# CAN.net
KiCad netlist of a schematic drawn in Altium Designer
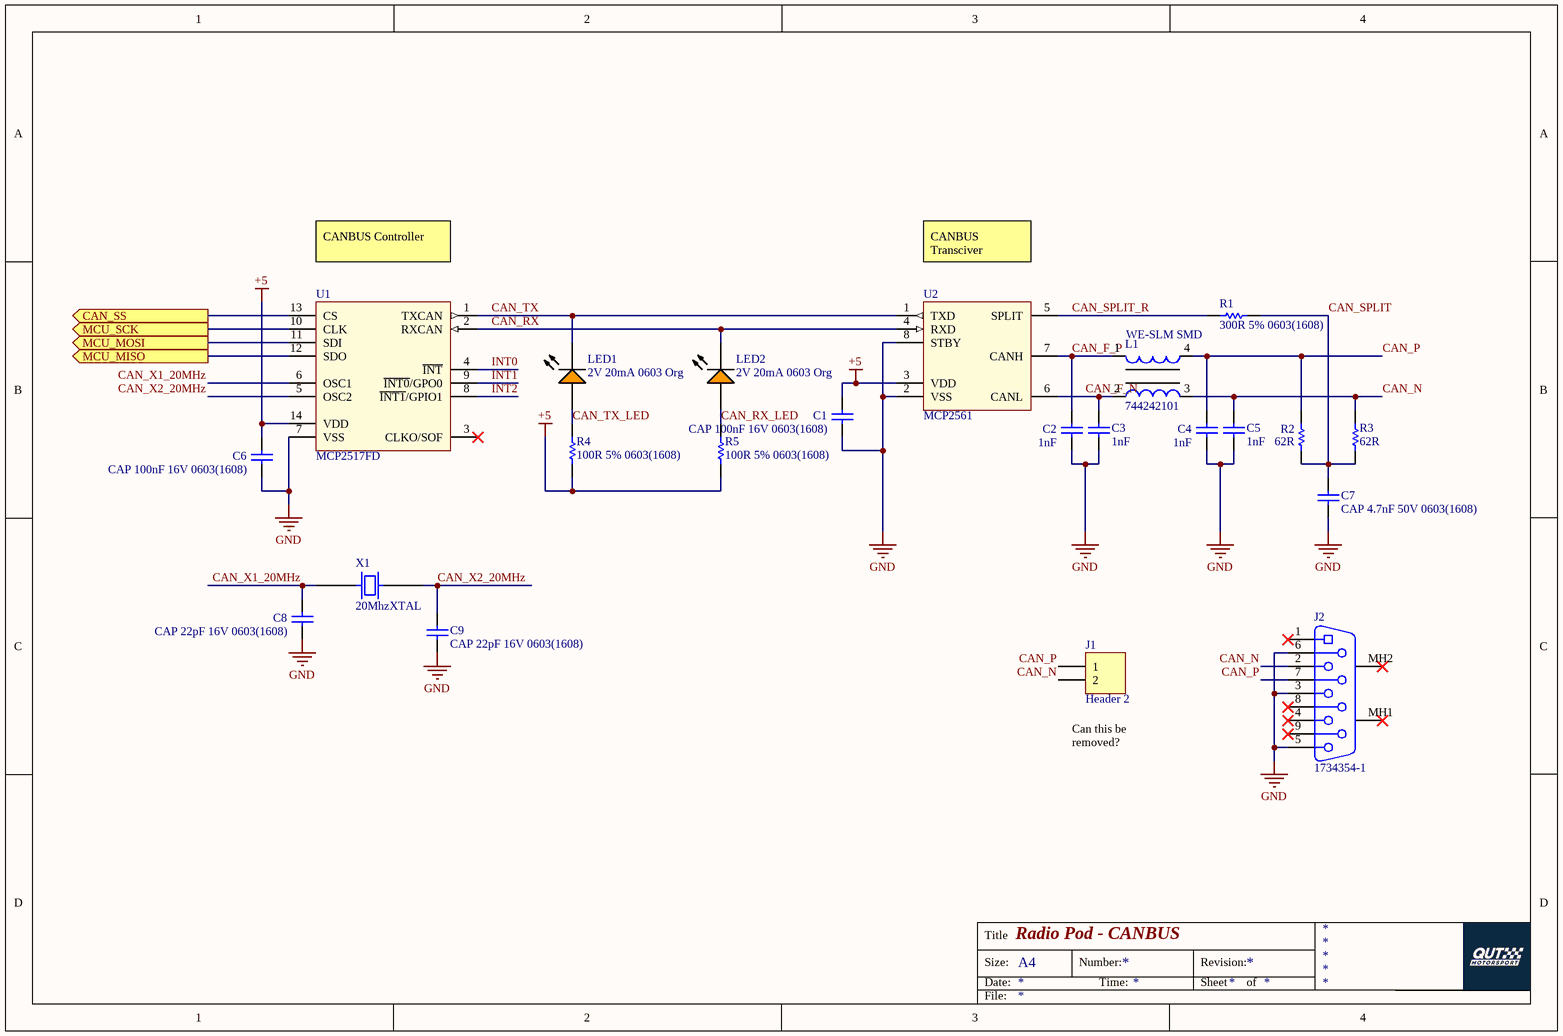
[diagram p0: CAN.SchDoc]

(export (version "E")
  (design (tool "Eeschema 10.0.6"))
  (components
    (comp (ref "C1")
      (value "CAP 100nF 16V 0603(1608)")
      (footprint "CAPC0603(1608)100_N")
      (description "CAP 100nF 16V ±10% 0603 (1608 Metric) Thickness 1mm SMD")
      (fields (field (name "TOLERANCE") "Â±10%"))
      (libsource (lib "Altium Content Vault") (part "CAP"))
    )
    (comp (ref "C2")
      (value "1nF")
      (footprint "CAPC0603(1608)100_M")
      (description "CAP 1nF 16V ±5% 0603 (1608 Metric) Thickness 1mm SMD")
      (fields (field (name "TOLERANCE") "Â±5%"))
      (libsource (lib "Altium Content Vault") (part "CAP"))
    )
    (comp (ref "C3")
      (value "1nF")
      (footprint "CAPC0603(1608)100_M")
      (description "CAP 1nF 16V ±5% 0603 (1608 Metric) Thickness 1mm SMD")
      (fields (field (name "TOLERANCE") "Â±5%"))
      (libsource (lib "Altium Content Vault") (part "CAP"))
    )
    (comp (ref "C4")
      (value "1nF")
      (footprint "CAPC0603(1608)100_M")
      (description "CAP 1nF 16V ±5% 0603 (1608 Metric) Thickness 1mm SMD")
      (fields (field (name "TOLERANCE") "Â±5%"))
      (libsource (lib "Altium Content Vault") (part "CAP"))
    )
    (comp (ref "C5")
      (value "1nF")
      (footprint "CAPC0603(1608)100_M")
      (description "CAP 1nF 16V ±5% 0603 (1608 Metric) Thickness 1mm SMD")
      (fields (field (name "TOLERANCE") "Â±5%"))
      (libsource (lib "Altium Content Vault") (part "CAP"))
    )
    (comp (ref "C6")
      (value "CAP 100nF 16V 0603(1608)")
      (footprint "CAPC0603(1608)100_N")
      (description "CAP 100nF 16V ±10% 0603 (1608 Metric) Thickness 1mm SMD")
      (fields (field (name "TOLERANCE") "Â±10%"))
      (libsource (lib "Altium Content Vault") (part "CAP"))
    )
    (comp (ref "C7")
      (value "CAP 4.7nF 50V 0603(1608)")
      (footprint "CAPC0603(1608)100_M")
      (description "CAP 4.7nF 50V ±5% 0603 (1608 Metric) Thickness 1mm SMD")
      (fields (field (name "TOLERANCE") "Â±5%"))
      (libsource (lib "Altium Content Vault") (part "CAP"))
    )
    (comp (ref "C8")
      (value "CAP 22pF 16V 0603(1608)")
      (footprint "CAPC0603(1608)100_N")
      (description "CAP 22pF 16V ±5% 0603 (1608 Metric) Thickness 1mm SMD")
      (fields (field (name "TOLERANCE") "Â±5%"))
      (libsource (lib "Altium Content Vault") (part "CAP"))
    )
    (comp (ref "C9")
      (value "CAP 22pF 16V 0603(1608)")
      (footprint "CAPC0603(1608)100_N")
      (description "CAP 22pF 16V ±5% 0603 (1608 Metric) Thickness 1mm SMD")
      (fields (field (name "TOLERANCE") "Â±5%"))
      (libsource (lib "Altium Content Vault") (part "CAP"))
    )
    (comp (ref "J1")
      (value "Header 2")
      (footprint "HDR1X2")
      (description "Header, 2-Pin")
      (fields (field (name "PUBLISHER") "Altium Limited"))
      (libsource (lib "Miscellaneous Connectors") (part "Header 2"))
    )
    (comp (ref "J2")
      (value "1734354-1")
      (footprint "TE-1734354-1-9_V")
      (description "D-Subminiature Socket, Pitch 1.385 mm, 9 Position, Height 12.5 mm, Tail Length 3.2 mm, RoHS, Tray")
      (fields (field (name "MANUFACTURER") "TE Connectivity"))
      (libsource (lib "Altium Content Vault") (part "CN-2S-2F-D9"))
    )
    (comp (ref "L1")
      (value "744242101")
      (footprint "WE-SLM")
      (description "SMD Common Mode Line Filter WE-SLM, L = 100 µH")
      (libsource (lib "Altium Content Vault") (part "PAS-IND-INDUCTOR-4C"))
    )
    (comp (ref "LED1")
      (value "2V 20mA 0603 Org")
      (footprint "KING-LED0603-25-ORANGE_V")
      (description "LED, SMT, 0603(1608), 0.25mm Tthickness, Super Bright Orange")
      (fields (field (name "PARTNUMBER") "APG1608SEKC/T"))
      (libsource (lib "Altium Content Vault") (part "KING-LED_ORANGE_A1K2-2"))
    )
    (comp (ref "LED2")
      (value "2V 20mA 0603 Org")
      (footprint "KING-LED0603-25-ORANGE_V")
      (description "LED, SMT, 0603(1608), 0.25mm Tthickness, Super Bright Orange")
      (fields (field (name "PARTNUMBER") "APG1608SEKC/T"))
      (libsource (lib "Altium Content Vault") (part "KING-LED_ORANGE_A1K2-2"))
    )
    (comp (ref "R1")
      (value "300R 5% 0603(1608)")
      (footprint "RESC0603(1608)_N")
      (description "300R 0.1W 5% 0603 (1608 Metric)  SMD")
      (fields (field (name "TOLERANCE") "5 %") (field (name "POWER") "0.1 W"))
      (libsource (lib "Altium Content Vault") (part "RES"))
    )
    (comp (ref "R2")
      (value "62R")
      (footprint "RESC1210(3225)_N")
      (description "62R 0.5W 5% 1210 (3225 Metric)  SMD")
      (fields (field (name "POWER") "0.5 W") (field (name "TOLERANCE") "5 %"))
      (libsource (lib "Altium Content Vault") (part "RES"))
    )
    (comp (ref "R3")
      (value "62R")
      (footprint "RESC1210(3225)_N")
      (description "62R 0.5W 5% 1210 (3225 Metric)  SMD")
      (fields (field (name "POWER") "0.5 W") (field (name "TOLERANCE") "5 %"))
      (libsource (lib "Altium Content Vault") (part "RES"))
    )
    (comp (ref "R4")
      (value "100R 5% 0603(1608)")
      (footprint "RESC0603(1608)_L")
      (description "100R 0.1W 5% 0603 (1608 Metric)  SMD")
      (fields (field (name "TOLERANCE") "5 %") (field (name "POWER") "0.1 W"))
      (libsource (lib "Altium Content Vault") (part "RES"))
    )
    (comp (ref "R5")
      (value "100R 5% 0603(1608)")
      (footprint "RESC0603(1608)_L")
      (description "100R 0.1W 5% 0603 (1608 Metric)  SMD")
      (fields (field (name "TOLERANCE") "5 %") (field (name "POWER") "0.1 W"))
      (libsource (lib "Altium Content Vault") (part "RES"))
    )
    (comp (ref "U1")
      (value "MCP2517FD")
      (footprint "MCP2517FD SOIC")
      (libsource (lib "QUTMS_CANLibrary") (part "MCP2517FD"))
    )
    (comp (ref "U2")
      (value "MCP2561")
      (footprint "MCP2561 SOIC")
      (libsource (lib "QUTMS_CANLibrary") (part "MCP2561"))
    )
    (comp (ref "X1")
      (value "20MhzXTAL")
      (footprint "HC49")
      (libsource (lib "Relays") (part "Crystral 20Mhz"))
    )
  )
  (nets
    (net (code "1") (name "+5") (class "Default")
      (node (ref "C1") (pin "2") (pinfunction "2_2") (pintype "passive"))
      (node (ref "C6") (pin "2") (pinfunction "2_2") (pintype "passive"))
      (node (ref "R4") (pin "2") (pinfunction "2_2") (pintype "passive"))
      (node (ref "R5") (pin "2") (pinfunction "2_2") (pintype "passive"))
      (node (ref "U1") (pin "14") (pinfunction "VDD_14") (pintype "passive"))
      (node (ref "U2") (pin "3") (pinfunction "VDD_3") (pintype "passive"))
    )
    (net (code "2") (name "/CAN_F_N") (class "Default")
      (node (ref "C3") (pin "2") (pinfunction "2_2") (pintype "passive"))
      (node (ref "L1") (pin "2") (pinfunction "2_2") (pintype "passive"))
      (node (ref "U2") (pin "6") (pinfunction "CANL_6") (pintype "passive"))
    )
    (net (code "3") (name "/CAN_F_P") (class "Default")
      (node (ref "C2") (pin "2") (pinfunction "2_2") (pintype "passive"))
      (node (ref "L1") (pin "1") (pinfunction "1_1") (pintype "passive"))
      (node (ref "U2") (pin "7") (pinfunction "CANH_7") (pintype "passive"))
    )
    (net (code "4") (name "/CAN_N") (class "Default")
      (node (ref "C5") (pin "2") (pinfunction "2_2") (pintype "passive"))
      (node (ref "J1") (pin "2") (pinfunction "2_2") (pintype "passive"))
      (node (ref "J2") (pin "2") (pinfunction "2_2") (pintype "passive"))
      (node (ref "L1") (pin "3") (pinfunction "3_3") (pintype "passive"))
      (node (ref "R3") (pin "2") (pinfunction "2_2") (pintype "passive"))
    )
    (net (code "5") (name "/CAN_P") (class "Default")
      (node (ref "C4") (pin "2") (pinfunction "2_2") (pintype "passive"))
      (node (ref "J1") (pin "1") (pinfunction "1_1") (pintype "passive"))
      (node (ref "J2") (pin "7") (pinfunction "7_7") (pintype "passive"))
      (node (ref "L1") (pin "4") (pinfunction "4_4") (pintype "passive"))
      (node (ref "R2") (pin "2") (pinfunction "2_2") (pintype "passive"))
    )
    (net (code "6") (name "/CAN_RX") (class "Default")
      (node (ref "LED2") (pin "2") (pinfunction "K_2") (pintype "passive"))
      (node (ref "U1") (pin "2") (pinfunction "RXCAN_2") (pintype "input"))
      (node (ref "U2") (pin "4") (pinfunction "RXD_4") (pintype "input"))
    )
    (net (code "7") (name "/CAN_RX_LED") (class "Default")
      (node (ref "LED2") (pin "1") (pinfunction "A_1") (pintype "passive"))
      (node (ref "R5") (pin "1") (pinfunction "1_1") (pintype "passive"))
    )
    (net (code "8") (name "/CAN_SPLIT") (class "Default")
      (node (ref "C7") (pin "2") (pinfunction "2_2") (pintype "passive"))
      (node (ref "R1") (pin "2") (pinfunction "2_2") (pintype "passive"))
      (node (ref "R2") (pin "1") (pinfunction "1_1") (pintype "passive"))
      (node (ref "R3") (pin "1") (pinfunction "1_1") (pintype "passive"))
    )
    (net (code "9") (name "/CAN_SPLIT_R") (class "Default")
      (node (ref "R1") (pin "1") (pinfunction "1_1") (pintype "passive"))
      (node (ref "U2") (pin "5") (pinfunction "SPLIT_5") (pintype "passive"))
    )
    (net (code "10") (name "/CAN_SS") (class "Default")
      (node (ref "U1") (pin "13") (pinfunction "CS_13") (pintype "passive"))
    )
    (net (code "11") (name "/CAN_TX") (class "Default")
      (node (ref "LED1") (pin "2") (pinfunction "K_2") (pintype "passive"))
      (node (ref "U1") (pin "1") (pinfunction "TXCAN_1") (pintype "output"))
      (node (ref "U2") (pin "1") (pinfunction "TXD_1") (pintype "output"))
    )
    (net (code "12") (name "/CAN_TX_LED") (class "Default")
      (node (ref "LED1") (pin "1") (pinfunction "A_1") (pintype "passive"))
      (node (ref "R4") (pin "1") (pinfunction "1_1") (pintype "passive"))
    )
    (net (code "13") (name "/CAN_X1_20MHz") (class "Default")
      (node (ref "C8") (pin "2") (pinfunction "2_2") (pintype "passive"))
      (node (ref "U1") (pin "6") (pinfunction "OSC1_6") (pintype "passive"))
      (node (ref "X1") (pin "1") (pinfunction "45_1") (pintype "passive"))
    )
    (net (code "14") (name "/CAN_X2_20MHz") (class "Default")
      (node (ref "C9") (pin "1") (pinfunction "1_1") (pintype "passive"))
      (node (ref "U1") (pin "5") (pinfunction "OSC2_5") (pintype "passive"))
      (node (ref "X1") (pin "2") (pinfunction "46_2") (pintype "passive"))
    )
    (net (code "15") (name "/INT0") (class "Default")
      (node (ref "U1") (pin "4") (pinfunction "~{INT}_4") (pintype "passive"))
    )
    (net (code "16") (name "/INT1") (class "Default")
      (node (ref "U1") (pin "9") (pinfunction "~{INT0}/GPO0_9") (pintype "passive"))
    )
    (net (code "17") (name "/INT2") (class "Default")
      (node (ref "U1") (pin "8") (pinfunction "~{INT1}/GPIO1_8") (pintype "passive"))
    )
    (net (code "18") (name "/MCU_MISO") (class "Default")
      (node (ref "U1") (pin "12") (pinfunction "SDO_12") (pintype "passive"))
    )
    (net (code "19") (name "/MCU_MOSI") (class "Default")
      (node (ref "U1") (pin "11") (pinfunction "SDI_11") (pintype "passive"))
    )
    (net (code "20") (name "/MCU_SCK") (class "Default")
      (node (ref "U1") (pin "10") (pinfunction "CLK_10") (pintype "passive"))
    )
    (net (code "21") (name "GND") (class "Default")
      (node (ref "C1") (pin "1") (pinfunction "1_1") (pintype "passive"))
      (node (ref "C2") (pin "1") (pinfunction "1_1") (pintype "passive"))
      (node (ref "C3") (pin "1") (pinfunction "1_1") (pintype "passive"))
      (node (ref "C4") (pin "1") (pinfunction "1_1") (pintype "passive"))
      (node (ref "C5") (pin "1") (pinfunction "1_1") (pintype "passive"))
      (node (ref "C6") (pin "1") (pinfunction "1_1") (pintype "passive"))
      (node (ref "C7") (pin "1") (pinfunction "1_1") (pintype "passive"))
      (node (ref "C8") (pin "1") (pinfunction "1_1") (pintype "passive"))
      (node (ref "C9") (pin "2") (pinfunction "2_2") (pintype "passive"))
      (node (ref "J2") (pin "3") (pinfunction "3_3") (pintype "passive"))
      (node (ref "J2") (pin "5") (pinfunction "5_5") (pintype "passive"))
      (node (ref "J2") (pin "6") (pinfunction "6_6") (pintype "passive"))
      (node (ref "U1") (pin "7") (pinfunction "VSS_7") (pintype "passive"))
      (node (ref "U2") (pin "2") (pinfunction "VSS_2") (pintype "passive"))
      (node (ref "U2") (pin "8") (pinfunction "STBY_8") (pintype "passive"))
    )
    (net (code "22") (name "unconnected-(J2-Pad1)") (class "Default")
      (node (ref "J2") (pin "1") (pinfunction "1_1") (pintype "passive+no_connect"))
    )
    (net (code "23") (name "unconnected-(J2-Pad4)") (class "Default")
      (node (ref "J2") (pin "4") (pinfunction "4_4") (pintype "passive+no_connect"))
    )
    (net (code "24") (name "unconnected-(J2-Pad8)") (class "Default")
      (node (ref "J2") (pin "8") (pinfunction "8_8") (pintype "passive+no_connect"))
    )
    (net (code "25") (name "unconnected-(J2-Pad9)") (class "Default")
      (node (ref "J2") (pin "9") (pinfunction "9_9") (pintype "passive+no_connect"))
    )
    (net (code "26") (name "unconnected-(J2-PadMH1)") (class "Default")
      (node (ref "J2") (pin "MH1") (pinfunction "MH1_MH1") (pintype "passive+no_connect"))
    )
    (net (code "27") (name "unconnected-(J2-PadMH2)") (class "Default")
      (node (ref "J2") (pin "MH2") (pinfunction "MH2_MH2") (pintype "passive+no_connect"))
    )
    (net (code "28") (name "unconnected-(U1-CLKO{slash}SOF-Pad3)") (class "Default")
      (node (ref "U1") (pin "3") (pinfunction "CLKO/SOF_3") (pintype "passive+no_connect"))
    )
  )
)
